# RFID_reader_v2.net
KiCad netlist of a schematic drawn in EAGLE
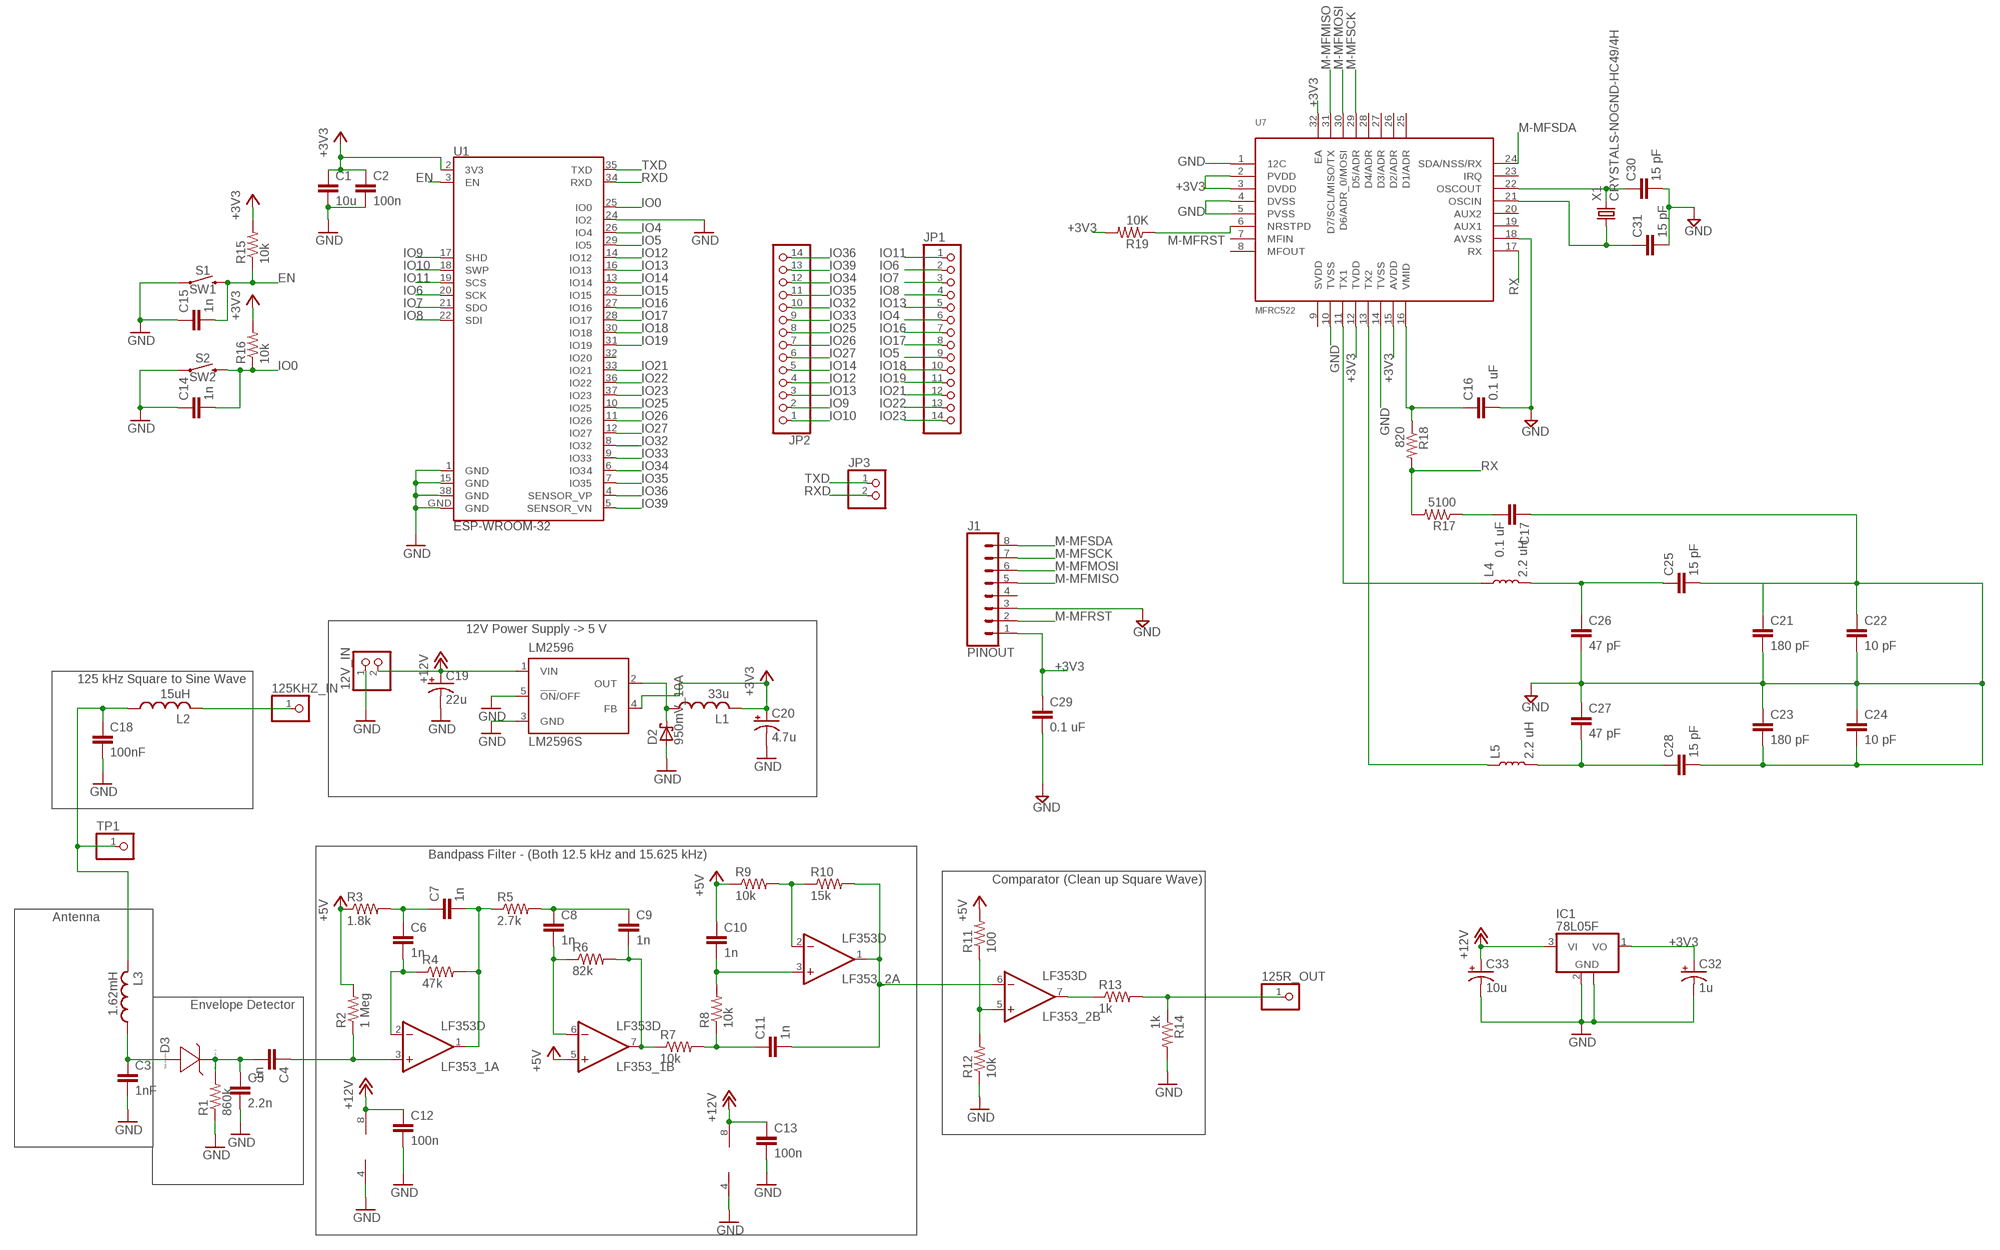
[diagram p0: schematic, sheet 1]

(export (version "E")
  (design (tool "Eeschema 10.0.6"))
  (components
    (comp (ref "12V_IN")
      (value "PINHD-1X2")
      (footprint "eagle-import:1X02")
      (libsource (lib "eagle-import") (part "PINHD-1X2"))
    )
    (comp (ref "125KHZ_IN")
      (value "PINHD-1X1")
      (footprint "eagle-import:1X01")
      (libsource (lib "eagle-import") (part "PINHD-1X1"))
    )
    (comp (ref "125R_OUT")
      (value "PINHD-1X1")
      (footprint "eagle-import:1X01")
      (libsource (lib "eagle-import") (part "PINHD-1X1"))
    )
    (comp (ref "C1")
      (value "10u")
      (footprint "eagle-import:C0805")
      (libsource (lib "eagle-import") (part "C-EUC0805"))
    )
    (comp (ref "C2")
      (value "100n")
      (footprint "eagle-import:C0805")
      (libsource (lib "eagle-import") (part "C-EUC0805"))
    )
    (comp (ref "C3")
      (value "1nF")
      (footprint "eagle-import:C0805")
      (libsource (lib "eagle-import") (part "C-EUC0805"))
    )
    (comp (ref "C4")
      (value "1n")
      (footprint "eagle-import:C0805")
      (libsource (lib "eagle-import") (part "C-EUC0805"))
    )
    (comp (ref "C5")
      (value "2.2n")
      (footprint "eagle-import:C0805")
      (libsource (lib "eagle-import") (part "C-EUC0805"))
    )
    (comp (ref "C6")
      (value "1n")
      (footprint "eagle-import:C0805")
      (libsource (lib "eagle-import") (part "C-EUC0805"))
    )
    (comp (ref "C7")
      (value "1n")
      (footprint "eagle-import:C0805")
      (libsource (lib "eagle-import") (part "C-EUC0805"))
    )
    (comp (ref "C8")
      (value "1n")
      (footprint "eagle-import:C0805")
      (libsource (lib "eagle-import") (part "C-EUC0805"))
    )
    (comp (ref "C9")
      (value "1n")
      (footprint "eagle-import:C0805")
      (libsource (lib "eagle-import") (part "C-EUC0805"))
    )
    (comp (ref "C10")
      (value "1n")
      (footprint "eagle-import:C0805")
      (libsource (lib "eagle-import") (part "C-EUC0805"))
    )
    (comp (ref "C11")
      (value "1n")
      (footprint "eagle-import:C0805")
      (libsource (lib "eagle-import") (part "C-EUC0805"))
    )
    (comp (ref "C12")
      (value "100n")
      (footprint "eagle-import:C0805")
      (libsource (lib "eagle-import") (part "C-EUC0805"))
    )
    (comp (ref "C13")
      (value "100n")
      (footprint "eagle-import:C0805")
      (libsource (lib "eagle-import") (part "C-EUC0805"))
    )
    (comp (ref "C14")
      (value "1n")
      (footprint "eagle-import:C0805")
      (libsource (lib "eagle-import") (part "C-EUC0805"))
    )
    (comp (ref "C15")
      (value "1n")
      (footprint "eagle-import:C0805")
      (libsource (lib "eagle-import") (part "C-EUC0805"))
    )
    (comp (ref "C16")
      (value "0.1 uF")
      (footprint "eagle-import:C0603")
      (libsource (lib "eagle-import") (part "C-EUC0603"))
    )
    (comp (ref "C17")
      (value "0.1 uF")
      (footprint "eagle-import:C0603")
      (libsource (lib "eagle-import") (part "C-EUC0603"))
    )
    (comp (ref "C18")
      (value "100nF")
      (footprint "eagle-import:C0805")
      (libsource (lib "eagle-import") (part "C-EUC0805"))
    )
    (comp (ref "C19")
      (value "22u")
      (footprint "eagle-import:SANYO-OSCON_SMD_B6")
      (libsource (lib "eagle-import") (part "CPOL-USSANYO_SMD_B6"))
    )
    (comp (ref "C20")
      (value "4.7u")
      (footprint "eagle-import:SMC_C")
      (libsource (lib "eagle-import") (part "CPOL-USSMCC"))
    )
    (comp (ref "C21")
      (value "180 pF")
      (footprint "eagle-import:C0603")
      (libsource (lib "eagle-import") (part "C-EUC0603"))
    )
    (comp (ref "C22")
      (value "10 pF")
      (footprint "eagle-import:C0603")
      (libsource (lib "eagle-import") (part "C-EUC0603"))
    )
    (comp (ref "C23")
      (value "180 pF")
      (footprint "eagle-import:C0603")
      (libsource (lib "eagle-import") (part "C-EUC0603"))
    )
    (comp (ref "C24")
      (value "10 pF")
      (footprint "eagle-import:C0603")
      (libsource (lib "eagle-import") (part "C-EUC0603"))
    )
    (comp (ref "C25")
      (value "15 pF")
      (footprint "eagle-import:C0603")
      (libsource (lib "eagle-import") (part "C-EUC0603"))
    )
    (comp (ref "C26")
      (value "47 pF")
      (footprint "eagle-import:C0603")
      (libsource (lib "eagle-import") (part "C-EUC0603"))
    )
    (comp (ref "C27")
      (value "47 pF")
      (footprint "eagle-import:C0603")
      (libsource (lib "eagle-import") (part "C-EUC0603"))
    )
    (comp (ref "C28")
      (value "15 pF")
      (footprint "eagle-import:C0603")
      (libsource (lib "eagle-import") (part "C-EUC0603"))
    )
    (comp (ref "C29")
      (value "0.1 uF")
      (footprint "eagle-import:C0603")
      (libsource (lib "eagle-import") (part "C-EUC0603"))
    )
    (comp (ref "C30")
      (value "15 pF")
      (footprint "eagle-import:C0603")
      (libsource (lib "eagle-import") (part "C-EUC0603"))
    )
    (comp (ref "C31")
      (value "15 pF")
      (footprint "eagle-import:C0603")
      (libsource (lib "eagle-import") (part "C-EUC0603"))
    )
    (comp (ref "C32")
      (value "1u")
      (footprint "eagle-import:SMC_A")
      (libsource (lib "eagle-import") (part "CPOL-USSMCA"))
    )
    (comp (ref "C33")
      (value "10u")
      (footprint "eagle-import:SMC_C")
      (libsource (lib "eagle-import") (part "CPOL-USSMCC"))
    )
    (comp (ref "D2")
      (value "950mV_10A")
      (footprint "eagle-import:SMC")
      (libsource (lib "eagle-import") (part "SCHOTTKY-DIODESMC"))
    )
    (comp (ref "D3")
      (value "ZENER")
      (footprint "eagle-import:SOD123")
      (libsource (lib "eagle-import") (part "ZENER"))
    )
    (comp (ref "IC1")
      (value "78L05F")
      (footprint "eagle-import:SOT89")
      (libsource (lib "eagle-import") (part "78LF05"))
    )
    (comp (ref "J1")
      (value "PINOUT")
      (footprint "eagle-import:1X08_NO_SILK")
      (libsource (lib "eagle-import") (part "CONN_08NO_SILK_FEMALE_PTH"))
    )
    (comp (ref "JP1")
      (value "PINHD-1X14")
      (footprint "eagle-import:1X14")
      (libsource (lib "eagle-import") (part "PINHD-1X14"))
    )
    (comp (ref "JP2")
      (value "PINHD-1X14")
      (footprint "eagle-import:1X14")
      (libsource (lib "eagle-import") (part "PINHD-1X14"))
    )
    (comp (ref "JP3")
      (value "PINHD-1X2")
      (footprint "eagle-import:1X02")
      (libsource (lib "eagle-import") (part "PINHD-1X2"))
    )
    (comp (ref "L1")
      (value "33u")
      (footprint "eagle-import:0207_10")
      (libsource (lib "eagle-import") (part "L-US0207/10"))
    )
    (comp (ref "L2")
      (value "15uH")
      (footprint "eagle-import:L2012C")
      (libsource (lib "eagle-import") (part "L-USL2012C"))
    )
    (comp (ref "L3")
      (value "1.62mH")
      (footprint "eagle-import:0207_10")
      (libsource (lib "eagle-import") (part "L-US0207/10"))
    )
    (comp (ref "L4")
      (value "2.2 uH")
      (footprint "eagle-import:0603")
      (libsource (lib "eagle-import") (part "INDUCTOR-0603-33NH"))
    )
    (comp (ref "L5")
      (value "2.2 uH")
      (footprint "eagle-import:0603")
      (libsource (lib "eagle-import") (part "INDUCTOR-0603-33NH"))
    )
    (comp (ref "LF353_1")
      (value "LF353D")
      (footprint "eagle-import:SO08")
      (fields (field (name "SPICEPREFIX") "J"))
      (libsource (lib "eagle-import") (part "LF353D"))
    )
    (comp (ref "LF353_2")
      (value "LF353D")
      (footprint "eagle-import:SO08")
      (libsource (lib "eagle-import") (part "LF353D"))
    )
    (comp (ref "LM2596")
      (value "LM2596S")
      (footprint "eagle-import:TO263-5")
      (fields (field (name "MF") "NATIONAL SEMICONDUCTOR") (field (name "MPN") "LM2596S-ADJ/NOPB"))
      (libsource (lib "eagle-import") (part "LM2596S"))
    )
    (comp (ref "R1")
      (value "860k")
      (footprint "eagle-import:R0805")
      (libsource (lib "eagle-import") (part "R-US_R0805"))
    )
    (comp (ref "R2")
      (value "1 Meg")
      (footprint "eagle-import:R0805")
      (libsource (lib "eagle-import") (part "R-US_R0805"))
    )
    (comp (ref "R3")
      (value "1.8k")
      (footprint "eagle-import:R0805")
      (libsource (lib "eagle-import") (part "R-US_R0805"))
    )
    (comp (ref "R4")
      (value "47k")
      (footprint "eagle-import:R0805")
      (libsource (lib "eagle-import") (part "R-US_R0805"))
    )
    (comp (ref "R5")
      (value "2.7k")
      (footprint "eagle-import:R0805")
      (libsource (lib "eagle-import") (part "R-US_R0805"))
    )
    (comp (ref "R6")
      (value "82k")
      (footprint "eagle-import:R0805")
      (libsource (lib "eagle-import") (part "R-US_R0805"))
    )
    (comp (ref "R7")
      (value "10k")
      (footprint "eagle-import:R0805")
      (libsource (lib "eagle-import") (part "R-US_R0805"))
    )
    (comp (ref "R8")
      (value "10k")
      (footprint "eagle-import:R0805")
      (libsource (lib "eagle-import") (part "R-US_R0805"))
    )
    (comp (ref "R9")
      (value "10k")
      (footprint "eagle-import:R0805")
      (libsource (lib "eagle-import") (part "R-US_R0805"))
    )
    (comp (ref "R10")
      (value "15k")
      (footprint "eagle-import:R0805")
      (libsource (lib "eagle-import") (part "R-US_R0805"))
    )
    (comp (ref "R11")
      (value "100")
      (footprint "eagle-import:R0805")
      (libsource (lib "eagle-import") (part "R-US_R0805"))
    )
    (comp (ref "R12")
      (value "10k")
      (footprint "eagle-import:R0805")
      (libsource (lib "eagle-import") (part "R-US_R0805"))
    )
    (comp (ref "R13")
      (value "1k")
      (footprint "eagle-import:R0805")
      (libsource (lib "eagle-import") (part "R-US_R0805"))
    )
    (comp (ref "R14")
      (value "1k")
      (footprint "eagle-import:R0805")
      (libsource (lib "eagle-import") (part "R-US_R0805"))
    )
    (comp (ref "R15")
      (value "10k")
      (footprint "eagle-import:R0805")
      (libsource (lib "eagle-import") (part "R-US_R0805"))
    )
    (comp (ref "R16")
      (value "10k")
      (footprint "eagle-import:R0805")
      (libsource (lib "eagle-import") (part "R-US_R0805"))
    )
    (comp (ref "R17")
      (value "5100")
      (footprint "eagle-import:R0603")
      (libsource (lib "eagle-import") (part "R-US_R0603"))
    )
    (comp (ref "R18")
      (value "820")
      (footprint "eagle-import:R0603")
      (libsource (lib "eagle-import") (part "R-US_R0603"))
    )
    (comp (ref "R19")
      (value "10K")
      (footprint "eagle-import:R0603")
      (libsource (lib "eagle-import") (part "R-US_R0603"))
    )
    (comp (ref "S1")
      (value "SW1")
      (footprint "eagle-import:TACTILE_SWITCH_SMD_6.0X3.5MM")
      (libsource (lib "eagle-import") (part "MOMENTARY-SWITCH-SPST-SMD-6.0X3.5MM"))
    )
    (comp (ref "S2")
      (value "SW2")
      (footprint "eagle-import:TACTILE_SWITCH_SMD_6.0X3.5MM")
      (libsource (lib "eagle-import") (part "MOMENTARY-SWITCH-SPST-SMD-6.0X3.5MM"))
    )
    (comp (ref "TP1")
      (value "PINHD-1X1")
      (footprint "eagle-import:1X01")
      (libsource (lib "eagle-import") (part "PINHD-1X1"))
    )
    (comp (ref "U1")
      (value "ESP-WROOM-32")
      (footprint "eagle-import:ESP-WROOM-32")
      (libsource (lib "eagle-import") (part "ESP-WROOM-32"))
    )
    (comp (ref "U7")
      (value "MFRC522")
      (footprint "eagle-import:MFR522")
      (libsource (lib "eagle-import") (part "MFRC522"))
    )
    (comp (ref "X1")
      (value "CRYSTALS-NOGND-HC49/4H")
      (footprint "eagle-import:HC49")
      (libsource (lib "eagle-import") (part "CRYSTALS-NOGND-HC49/4H"))
    )
  )
  (nets
    (net (code "1") (name "+3V3") (class "Default")
      (node (ref "C1") (pin "1") (pinfunction "1_1") (pintype "passive"))
      (node (ref "C2") (pin "1") (pinfunction "1_1") (pintype "passive"))
      (node (ref "C20") (pin "+") (pinfunction "+_+") (pintype "passive"))
      (node (ref "C29") (pin "1") (pinfunction "1_1") (pintype "passive"))
      (node (ref "C32") (pin "+") (pinfunction "+_+") (pintype "passive"))
      (node (ref "IC1") (pin "1") (pinfunction "VO_1") (pintype "passive"))
      (node (ref "J1") (pin "1") (pinfunction "1_1") (pintype "passive"))
      (node (ref "L1") (pin "2") (pinfunction "2_2") (pintype "passive"))
      (node (ref "LM2596") (pin "4") (pinfunction "FB_4") (pintype "input"))
      (node (ref "R15") (pin "2") (pinfunction "2_2") (pintype "passive"))
      (node (ref "R16") (pin "2") (pinfunction "2_2") (pintype "passive"))
      (node (ref "R19") (pin "2") (pinfunction "2_2") (pintype "passive"))
      (node (ref "U1") (pin "2") (pinfunction "3V3_2") (pintype "bidirectional"))
      (node (ref "U7") (pin "12") (pinfunction "TVDD_12") (pintype "bidirectional"))
      (node (ref "U7") (pin "15") (pinfunction "AVDD_15") (pintype "bidirectional"))
      (node (ref "U7") (pin "2") (pinfunction "PVDD_2") (pintype "bidirectional"))
      (node (ref "U7") (pin "3") (pinfunction "DVDD_3") (pintype "bidirectional"))
      (node (ref "U7") (pin "32") (pinfunction "EA_32") (pintype "bidirectional"))
    )
    (net (code "2") (name "+5V") (class "Default")
      (node (ref "C10") (pin "1") (pinfunction "1_1") (pintype "passive"))
      (node (ref "LF353_1") (pin "5") (pinfunction "+IN_5") (pintype "input"))
      (node (ref "R11") (pin "2") (pinfunction "2_2") (pintype "passive"))
      (node (ref "R2") (pin "2") (pinfunction "2_2") (pintype "passive"))
      (node (ref "R3") (pin "1") (pinfunction "1_1") (pintype "passive"))
      (node (ref "R9") (pin "1") (pinfunction "1_1") (pintype "passive"))
    )
    (net (code "3") (name "+12V") (class "Default")
      (node (ref "12V_IN") (pin "2") (pinfunction "2_2") (pintype "passive"))
      (node (ref "C12") (pin "1") (pinfunction "1_1") (pintype "passive"))
      (node (ref "C13") (pin "1") (pinfunction "1_1") (pintype "passive"))
      (node (ref "C19") (pin "+") (pinfunction "+_+") (pintype "passive"))
      (node (ref "C33") (pin "+") (pinfunction "+_+") (pintype "passive"))
      (node (ref "IC1") (pin "3") (pinfunction "VI_3") (pintype "input"))
      (node (ref "LF353_1") (pin "8") (pinfunction "V+_8") (pintype "power_in"))
      (node (ref "LF353_2") (pin "8") (pinfunction "V+_8") (pintype "power_in"))
      (node (ref "LM2596") (pin "1") (pinfunction "VIN_1") (pintype "input"))
    )
    (net (code "4") (name "/EN") (class "Default")
      (node (ref "C15") (pin "2") (pinfunction "2_2") (pintype "passive"))
      (node (ref "R15") (pin "1") (pinfunction "1_1") (pintype "passive"))
      (node (ref "S1") (pin "2") (pinfunction "2_2") (pintype "passive"))
      (node (ref "U1") (pin "3") (pinfunction "EN_3") (pintype "bidirectional"))
    )
    (net (code "5") (name "/IO0") (class "Default")
      (node (ref "C14") (pin "2") (pinfunction "2_2") (pintype "passive"))
      (node (ref "R16") (pin "1") (pinfunction "1_1") (pintype "passive"))
      (node (ref "S2") (pin "2") (pinfunction "2_2") (pintype "passive"))
      (node (ref "U1") (pin "25") (pinfunction "IO0_25") (pintype "bidirectional"))
    )
    (net (code "6") (name "/IO4") (class "Default")
      (node (ref "JP1") (pin "6") (pinfunction "6_6") (pintype "passive"))
      (node (ref "U1") (pin "26") (pinfunction "IO4_26") (pintype "bidirectional"))
    )
    (net (code "7") (name "/IO5") (class "Default")
      (node (ref "JP1") (pin "9") (pinfunction "9_9") (pintype "passive"))
      (node (ref "U1") (pin "29") (pinfunction "IO5_29") (pintype "bidirectional"))
    )
    (net (code "8") (name "/IO6") (class "Default")
      (node (ref "JP1") (pin "2") (pinfunction "2_2") (pintype "passive"))
      (node (ref "U1") (pin "20") (pinfunction "SCK_20") (pintype "bidirectional"))
    )
    (net (code "9") (name "/IO7") (class "Default")
      (node (ref "JP1") (pin "3") (pinfunction "3_3") (pintype "passive"))
      (node (ref "U1") (pin "21") (pinfunction "SDO_21") (pintype "bidirectional"))
    )
    (net (code "10") (name "/IO8") (class "Default")
      (node (ref "JP1") (pin "4") (pinfunction "4_4") (pintype "passive"))
      (node (ref "U1") (pin "22") (pinfunction "SDI_22") (pintype "bidirectional"))
    )
    (net (code "11") (name "/IO9") (class "Default")
      (node (ref "JP2") (pin "2") (pinfunction "2_2") (pintype "passive"))
      (node (ref "U1") (pin "17") (pinfunction "SHD_17") (pintype "bidirectional"))
    )
    (net (code "12") (name "/IO10") (class "Default")
      (node (ref "JP2") (pin "1") (pinfunction "1_1") (pintype "passive"))
      (node (ref "U1") (pin "18") (pinfunction "SWP_18") (pintype "bidirectional"))
    )
    (net (code "13") (name "/IO11") (class "Default")
      (node (ref "JP1") (pin "1") (pinfunction "1_1") (pintype "passive"))
      (node (ref "U1") (pin "19") (pinfunction "SCS_19") (pintype "bidirectional"))
    )
    (net (code "14") (name "/IO12") (class "Default")
      (node (ref "JP2") (pin "4") (pinfunction "4_4") (pintype "passive"))
      (node (ref "U1") (pin "14") (pinfunction "IO12_14") (pintype "bidirectional"))
    )
    (net (code "15") (name "/IO13") (class "Default")
      (node (ref "JP1") (pin "5") (pinfunction "5_5") (pintype "passive"))
      (node (ref "JP2") (pin "3") (pinfunction "3_3") (pintype "passive"))
      (node (ref "U1") (pin "16") (pinfunction "IO13_16") (pintype "bidirectional"))
    )
    (net (code "16") (name "/IO14") (class "Default")
      (node (ref "JP2") (pin "5") (pinfunction "5_5") (pintype "passive"))
      (node (ref "U1") (pin "13") (pinfunction "IO14_13") (pintype "bidirectional"))
    )
    (net (code "17") (name "/IO15") (class "Default")
      (node (ref "U1") (pin "23") (pinfunction "IO15_23") (pintype "bidirectional"))
    )
    (net (code "18") (name "/IO16") (class "Default")
      (node (ref "JP1") (pin "7") (pinfunction "7_7") (pintype "passive"))
      (node (ref "U1") (pin "27") (pinfunction "IO16_27") (pintype "bidirectional"))
    )
    (net (code "19") (name "/IO17") (class "Default")
      (node (ref "JP1") (pin "8") (pinfunction "8_8") (pintype "passive"))
      (node (ref "U1") (pin "28") (pinfunction "IO17_28") (pintype "bidirectional"))
    )
    (net (code "20") (name "/IO18") (class "Default")
      (node (ref "JP1") (pin "10") (pinfunction "10_10") (pintype "passive"))
      (node (ref "U1") (pin "30") (pinfunction "IO18_30") (pintype "bidirectional"))
    )
    (net (code "21") (name "/IO19") (class "Default")
      (node (ref "JP1") (pin "11") (pinfunction "11_11") (pintype "passive"))
      (node (ref "U1") (pin "31") (pinfunction "IO19_31") (pintype "bidirectional"))
    )
    (net (code "22") (name "/IO21") (class "Default")
      (node (ref "JP1") (pin "12") (pinfunction "12_12") (pintype "passive"))
      (node (ref "U1") (pin "33") (pinfunction "IO21_33") (pintype "bidirectional"))
    )
    (net (code "23") (name "/IO22") (class "Default")
      (node (ref "JP1") (pin "13") (pinfunction "13_13") (pintype "passive"))
      (node (ref "U1") (pin "36") (pinfunction "IO22_36") (pintype "bidirectional"))
    )
    (net (code "24") (name "/IO23") (class "Default")
      (node (ref "JP1") (pin "14") (pinfunction "14_14") (pintype "passive"))
      (node (ref "U1") (pin "37") (pinfunction "IO23_37") (pintype "bidirectional"))
    )
    (net (code "25") (name "/IO25") (class "Default")
      (node (ref "JP2") (pin "8") (pinfunction "8_8") (pintype "passive"))
      (node (ref "U1") (pin "10") (pinfunction "IO25_10") (pintype "bidirectional"))
    )
    (net (code "26") (name "/IO26") (class "Default")
      (node (ref "JP2") (pin "7") (pinfunction "7_7") (pintype "passive"))
      (node (ref "U1") (pin "11") (pinfunction "IO26_11") (pintype "bidirectional"))
    )
    (net (code "27") (name "/IO27") (class "Default")
      (node (ref "JP2") (pin "6") (pinfunction "6_6") (pintype "passive"))
      (node (ref "U1") (pin "12") (pinfunction "IO27_12") (pintype "bidirectional"))
    )
    (net (code "28") (name "/IO32") (class "Default")
      (node (ref "JP2") (pin "10") (pinfunction "10_10") (pintype "passive"))
      (node (ref "U1") (pin "8") (pinfunction "IO32_8") (pintype "bidirectional"))
    )
    (net (code "29") (name "/IO33") (class "Default")
      (node (ref "JP2") (pin "9") (pinfunction "9_9") (pintype "passive"))
      (node (ref "U1") (pin "9") (pinfunction "IO33_9") (pintype "bidirectional"))
    )
    (net (code "30") (name "/IO34") (class "Default")
      (node (ref "JP2") (pin "12") (pinfunction "12_12") (pintype "passive"))
      (node (ref "U1") (pin "6") (pinfunction "IO34_6") (pintype "bidirectional"))
    )
    (net (code "31") (name "/IO35") (class "Default")
      (node (ref "JP2") (pin "11") (pinfunction "11_11") (pintype "passive"))
      (node (ref "U1") (pin "7") (pinfunction "IO35_7") (pintype "bidirectional"))
    )
    (net (code "32") (name "/IO36") (class "Default")
      (node (ref "JP2") (pin "14") (pinfunction "14_14") (pintype "passive"))
      (node (ref "U1") (pin "4") (pinfunction "SENSOR_VP_4") (pintype "bidirectional"))
    )
    (net (code "33") (name "/IO39") (class "Default")
      (node (ref "JP2") (pin "13") (pinfunction "13_13") (pintype "passive"))
      (node (ref "U1") (pin "5") (pinfunction "SENSOR_VN_5") (pintype "bidirectional"))
    )
    (net (code "34") (name "/M-MFMISO") (class "Default")
      (node (ref "J1") (pin "5") (pinfunction "5_5") (pintype "passive"))
      (node (ref "U7") (pin "31") (pinfunction "D7/SCL/MISO/TX_31") (pintype "bidirectional"))
    )
    (net (code "35") (name "/M-MFMOSI") (class "Default")
      (node (ref "J1") (pin "6") (pinfunction "6_6") (pintype "passive"))
      (node (ref "U7") (pin "30") (pinfunction "D6/ADR_0/MOSI_30") (pintype "bidirectional"))
    )
    (net (code "36") (name "/M-MFRST") (class "Default")
      (node (ref "J1") (pin "2") (pinfunction "2_2") (pintype "passive"))
      (node (ref "R19") (pin "1") (pinfunction "1_1") (pintype "passive"))
      (node (ref "U7") (pin "6") (pinfunction "NRSTPD_6") (pintype "bidirectional"))
    )
    (net (code "37") (name "/M-MFSCK") (class "Default")
      (node (ref "J1") (pin "7") (pinfunction "7_7") (pintype "passive"))
      (node (ref "U7") (pin "29") (pinfunction "D5/ADR_29") (pintype "bidirectional"))
    )
    (net (code "38") (name "/M-MFSDA") (class "Default")
      (node (ref "J1") (pin "8") (pinfunction "8_8") (pintype "passive"))
      (node (ref "U7") (pin "24") (pinfunction "SDA/NSS/RX_24") (pintype "bidirectional"))
    )
    (net (code "39") (name "/RX") (class "Default")
      (node (ref "R17") (pin "2") (pinfunction "2_2") (pintype "passive"))
      (node (ref "R18") (pin "2") (pinfunction "2_2") (pintype "passive"))
      (node (ref "U7") (pin "17") (pinfunction "RX_17") (pintype "bidirectional"))
    )
    (net (code "40") (name "/RXD") (class "Default")
      (node (ref "JP3") (pin "2") (pinfunction "2_2") (pintype "passive"))
      (node (ref "U1") (pin "34") (pinfunction "RXD_34") (pintype "bidirectional"))
    )
    (net (code "41") (name "/TXD") (class "Default")
      (node (ref "JP3") (pin "1") (pinfunction "1_1") (pintype "passive"))
      (node (ref "U1") (pin "35") (pinfunction "TXD_35") (pintype "bidirectional"))
    )
    (net (code "42") (name "GND") (class "Default")
      (node (ref "12V_IN") (pin "1") (pinfunction "1_1") (pintype "passive"))
      (node (ref "C1") (pin "2") (pinfunction "2_2") (pintype "passive"))
      (node (ref "C12") (pin "2") (pinfunction "2_2") (pintype "passive"))
      (node (ref "C13") (pin "2") (pinfunction "2_2") (pintype "passive"))
      (node (ref "C14") (pin "1") (pinfunction "1_1") (pintype "passive"))
      (node (ref "C15") (pin "1") (pinfunction "1_1") (pintype "passive"))
      (node (ref "C16") (pin "2") (pinfunction "2_2") (pintype "passive"))
      (node (ref "C17") (pin "1") (pinfunction "1_1") (pintype "passive"))
      (node (ref "C18") (pin "2") (pinfunction "2_2") (pintype "passive"))
      (node (ref "C19") (pin "-") (pinfunction "-_-") (pintype "passive"))
      (node (ref "C2") (pin "2") (pinfunction "2_2") (pintype "passive"))
      (node (ref "C20") (pin "-") (pinfunction "-_-") (pintype "passive"))
      (node (ref "C21") (pin "1") (pinfunction "1_1") (pintype "passive"))
      (node (ref "C21") (pin "2") (pinfunction "2_2") (pintype "passive"))
      (node (ref "C22") (pin "1") (pinfunction "1_1") (pintype "passive"))
      (node (ref "C22") (pin "2") (pinfunction "2_2") (pintype "passive"))
      (node (ref "C23") (pin "1") (pinfunction "1_1") (pintype "passive"))
      (node (ref "C23") (pin "2") (pinfunction "2_2") (pintype "passive"))
      (node (ref "C24") (pin "1") (pinfunction "1_1") (pintype "passive"))
      (node (ref "C24") (pin "2") (pinfunction "2_2") (pintype "passive"))
      (node (ref "C25") (pin "2") (pinfunction "2_2") (pintype "passive"))
      (node (ref "C26") (pin "2") (pinfunction "2_2") (pintype "passive"))
      (node (ref "C27") (pin "1") (pinfunction "1_1") (pintype "passive"))
      (node (ref "C28") (pin "2") (pinfunction "2_2") (pintype "passive"))
      (node (ref "C29") (pin "2") (pinfunction "2_2") (pintype "passive"))
      (node (ref "C3") (pin "2") (pinfunction "2_2") (pintype "passive"))
      (node (ref "C30") (pin "2") (pinfunction "2_2") (pintype "passive"))
      (node (ref "C31") (pin "2") (pinfunction "2_2") (pintype "passive"))
      (node (ref "C32") (pin "-") (pinfunction "-_-") (pintype "passive"))
      (node (ref "C33") (pin "-") (pinfunction "-_-") (pintype "passive"))
      (node (ref "C5") (pin "2") (pinfunction "2_2") (pintype "passive"))
      (node (ref "D2") (pin "A") (pinfunction "A_A") (pintype "passive"))
      (node (ref "IC1") (pin "2") (pinfunction "GND_2") (pintype "passive"))
      (node (ref "IC1") (pin "2@1") (pinfunction "GND_2@1") (pintype "passive"))
      (node (ref "J1") (pin "3") (pinfunction "3_3") (pintype "passive"))
      (node (ref "LF353_1") (pin "4") (pinfunction "V-_4") (pintype "power_in"))
      (node (ref "LF353_2") (pin "4") (pinfunction "V-_4") (pintype "power_in"))
      (node (ref "LM2596") (pin "3") (pinfunction "GND_3") (pintype "power_in"))
      (node (ref "LM2596") (pin "5") (pinfunction "~{ON}/OFF_5") (pintype "input"))
      (node (ref "R1") (pin "1") (pinfunction "1_1") (pintype "passive"))
      (node (ref "R12") (pin "1") (pinfunction "1_1") (pintype "passive"))
      (node (ref "R14") (pin "2") (pinfunction "2_2") (pintype "passive"))
      (node (ref "S1") (pin "1") (pinfunction "1_1") (pintype "passive"))
      (node (ref "S2") (pin "1") (pinfunction "1_1") (pintype "passive"))
      (node (ref "U1") (pin "1") (pinfunction "GND_1") (pintype "bidirectional"))
      (node (ref "U1") (pin "15") (pinfunction "GND_15") (pintype "bidirectional"))
      (node (ref "U1") (pin "24") (pinfunction "IO2_24") (pintype "bidirectional"))
      (node (ref "U1") (pin "38") (pinfunction "GND_38") (pintype "bidirectional"))
      (node (ref "U1") (pin "GND") (pinfunction "GND_GND") (pintype "bidirectional"))
      (node (ref "U7") (pin "1") (pinfunction "12C_1") (pintype "bidirectional"))
      (node (ref "U7") (pin "10") (pinfunction "TVSS_10") (pintype "bidirectional"))
      (node (ref "U7") (pin "14") (pinfunction "TVSS_14") (pintype "bidirectional"))
      (node (ref "U7") (pin "18") (pinfunction "AVSS_18") (pintype "bidirectional"))
      (node (ref "U7") (pin "4") (pinfunction "DVSS_4") (pintype "bidirectional"))
      (node (ref "U7") (pin "5") (pinfunction "PVSS_5") (pintype "bidirectional"))
    )
    (net (code "43") (name "Net-(125KHZ_IN-Pad1)") (class "Default")
      (node (ref "125KHZ_IN") (pin "1") (pinfunction "1_1") (pintype "passive"))
      (node (ref "L2") (pin "2") (pinfunction "2_2") (pintype "passive"))
    )
    (net (code "44") (name "Net-(125R_OUT-Pad1)") (class "Default")
      (node (ref "125R_OUT") (pin "1") (pinfunction "1_1") (pintype "passive"))
      (node (ref "R13") (pin "2") (pinfunction "2_2") (pintype "passive"))
      (node (ref "R14") (pin "1") (pinfunction "1_1") (pintype "passive"))
    )
    (net (code "45") (name "Net-(C6-Pad1)") (class "Default")
      (node (ref "C6") (pin "1") (pinfunction "1_1") (pintype "passive"))
      (node (ref "C7") (pin "1") (pinfunction "1_1") (pintype "passive"))
      (node (ref "R3") (pin "2") (pinfunction "2_2") (pintype "passive"))
    )
    (net (code "46") (name "Net-(C8-Pad1)") (class "Default")
      (node (ref "C8") (pin "1") (pinfunction "1_1") (pintype "passive"))
      (node (ref "C9") (pin "1") (pinfunction "1_1") (pintype "passive"))
      (node (ref "R5") (pin "2") (pinfunction "2_2") (pintype "passive"))
    )
    (net (code "47") (name "Net-(C11-Pad1)") (class "Default")
      (node (ref "C11") (pin "1") (pinfunction "1_1") (pintype "passive"))
      (node (ref "R7") (pin "2") (pinfunction "2_2") (pintype "passive"))
      (node (ref "R8") (pin "1") (pinfunction "1_1") (pintype "passive"))
    )
    (net (code "48") (name "Net-(C17-Pad2)") (class "Default")
      (node (ref "C17") (pin "2") (pinfunction "2_2") (pintype "passive"))
      (node (ref "R17") (pin "1") (pinfunction "1_1") (pintype "passive"))
    )
    (net (code "49") (name "Net-(C18-Pad1)") (class "Default")
      (node (ref "C18") (pin "1") (pinfunction "1_1") (pintype "passive"))
      (node (ref "L2") (pin "1") (pinfunction "1_1") (pintype "passive"))
      (node (ref "L3") (pin "2") (pinfunction "2_2") (pintype "passive"))
      (node (ref "TP1") (pin "1") (pinfunction "1_1") (pintype "passive"))
    )
    (net (code "50") (name "Net-(C25-Pad1)") (class "Default")
      (node (ref "C25") (pin "1") (pinfunction "1_1") (pintype "passive"))
      (node (ref "C26") (pin "1") (pinfunction "1_1") (pintype "passive"))
      (node (ref "L4") (pin "2") (pinfunction "2_2") (pintype "passive"))
    )
    (net (code "51") (name "Net-(C27-Pad2)") (class "Default")
      (node (ref "C27") (pin "2") (pinfunction "2_2") (pintype "passive"))
      (node (ref "C28") (pin "1") (pinfunction "1_1") (pintype "passive"))
      (node (ref "L5") (pin "2") (pinfunction "2_2") (pintype "passive"))
    )
    (net (code "52") (name "Net-(D3-+)") (class "Default")
      (node (ref "C3") (pin "1") (pinfunction "1_1") (pintype "passive"))
      (node (ref "D3") (pin "A") (pinfunction "+_A") (pintype "passive"))
      (node (ref "L3") (pin "1") (pinfunction "1_1") (pintype "passive"))
    )
    (net (code "53") (name "Net-(D3--)") (class "Default")
      (node (ref "C4") (pin "2") (pinfunction "2_2") (pintype "passive"))
      (node (ref "C5") (pin "1") (pinfunction "1_1") (pintype "passive"))
      (node (ref "D3") (pin "C") (pinfunction "-_C") (pintype "passive"))
      (node (ref "R1") (pin "2") (pinfunction "2_2") (pintype "passive"))
    )
    (net (code "54") (name "Net-(LF353_1A-+IN)") (class "Default")
      (node (ref "C4") (pin "1") (pinfunction "1_1") (pintype "passive"))
      (node (ref "LF353_1") (pin "3") (pinfunction "+IN_3") (pintype "input"))
      (node (ref "R2") (pin "1") (pinfunction "1_1") (pintype "passive"))
    )
    (net (code "55") (name "Net-(LF353_1A--IN)") (class "Default")
      (node (ref "C6") (pin "2") (pinfunction "2_2") (pintype "passive"))
      (node (ref "LF353_1") (pin "2") (pinfunction "-IN_2") (pintype "input"))
      (node (ref "R4") (pin "1") (pinfunction "1_1") (pintype "passive"))
    )
    (net (code "56") (name "Net-(LF353_1A-OUT)") (class "Default")
      (node (ref "C7") (pin "2") (pinfunction "2_2") (pintype "passive"))
      (node (ref "LF353_1") (pin "1") (pinfunction "OUT_1") (pintype "output"))
      (node (ref "R4") (pin "2") (pinfunction "2_2") (pintype "passive"))
      (node (ref "R5") (pin "1") (pinfunction "1_1") (pintype "passive"))
    )
    (net (code "57") (name "Net-(LF353_1B--IN)") (class "Default")
      (node (ref "C8") (pin "2") (pinfunction "2_2") (pintype "passive"))
      (node (ref "LF353_1") (pin "6") (pinfunction "-IN_6") (pintype "input"))
      (node (ref "R6") (pin "1") (pinfunction "1_1") (pintype "passive"))
    )
    (net (code "58") (name "Net-(LF353_1B-OUT)") (class "Default")
      (node (ref "C9") (pin "2") (pinfunction "2_2") (pintype "passive"))
      (node (ref "LF353_1") (pin "7") (pinfunction "OUT_7") (pintype "output"))
      (node (ref "R6") (pin "2") (pinfunction "2_2") (pintype "passive"))
      (node (ref "R7") (pin "1") (pinfunction "1_1") (pintype "passive"))
    )
    (net (code "59") (name "Net-(LF353_2A-+IN)") (class "Default")
      (node (ref "C10") (pin "2") (pinfunction "2_2") (pintype "passive"))
      (node (ref "LF353_2") (pin "3") (pinfunction "+IN_3") (pintype "input"))
      (node (ref "R8") (pin "2") (pinfunction "2_2") (pintype "passive"))
    )
    (net (code "60") (name "Net-(LF353_2A--IN)") (class "Default")
      (node (ref "LF353_2") (pin "2") (pinfunction "-IN_2") (pintype "input"))
      (node (ref "R10") (pin "1") (pinfunction "1_1") (pintype "passive"))
      (node (ref "R9") (pin "2") (pinfunction "2_2") (pintype "passive"))
    )
    (net (code "61") (name "Net-(LF353_2A-OUT)") (class "Default")
      (node (ref "C11") (pin "2") (pinfunction "2_2") (pintype "passive"))
      (node (ref "LF353_2") (pin "1") (pinfunction "OUT_1") (pintype "output"))
      (node (ref "LF353_2") (pin "6") (pinfunction "-IN_6") (pintype "input"))
      (node (ref "R10") (pin "2") (pinfunction "2_2") (pintype "passive"))
    )
    (net (code "62") (name "Net-(LF353_2B-+IN)") (class "Default")
      (node (ref "LF353_2") (pin "5") (pinfunction "+IN_5") (pintype "input"))
      (node (ref "R11") (pin "1") (pinfunction "1_1") (pintype "passive"))
      (node (ref "R12") (pin "2") (pinfunction "2_2") (pintype "passive"))
    )
    (net (code "63") (name "Net-(LF353_2B-OUT)") (class "Default")
      (node (ref "LF353_2") (pin "7") (pinfunction "OUT_7") (pintype "output"))
      (node (ref "R13") (pin "1") (pinfunction "1_1") (pintype "passive"))
    )
    (net (code "64") (name "Net-(LM2596-OUT)") (class "Default")
      (node (ref "D2") (pin "C") (pinfunction "C_C") (pintype "passive"))
      (node (ref "L1") (pin "1") (pinfunction "1_1") (pintype "passive"))
      (node (ref "LM2596") (pin "2") (pinfunction "OUT_2") (pintype "output"))
    )
    (net (code "65") (name "Net-(U7-OSCIN)") (class "Default")
      (node (ref "C31") (pin "1") (pinfunction "1_1") (pintype "passive"))
      (node (ref "U7") (pin "21") (pinfunction "OSCIN_21") (pintype "bidirectional"))
      (node (ref "X1") (pin "1") (pinfunction "1_1") (pintype "passive"))
    )
    (net (code "66") (name "Net-(U7-OSCOUT)") (class "Default")
      (node (ref "C30") (pin "1") (pinfunction "1_1") (pintype "passive"))
      (node (ref "U7") (pin "22") (pinfunction "OSCOUT_22") (pintype "bidirectional"))
      (node (ref "X1") (pin "2") (pinfunction "2_2") (pintype "passive"))
    )
    (net (code "67") (name "Net-(U7-TX1)") (class "Default")
      (node (ref "L4") (pin "1") (pinfunction "1_1") (pintype "passive"))
      (node (ref "U7") (pin "11") (pinfunction "TX1_11") (pintype "bidirectional"))
    )
    (net (code "68") (name "Net-(U7-TX2)") (class "Default")
      (node (ref "L5") (pin "1") (pinfunction "1_1") (pintype "passive"))
      (node (ref "U7") (pin "13") (pinfunction "TX2_13") (pintype "bidirectional"))
    )
    (net (code "69") (name "Net-(U7-VMID)") (class "Default")
      (node (ref "C16") (pin "1") (pinfunction "1_1") (pintype "passive"))
      (node (ref "R18") (pin "1") (pinfunction "1_1") (pintype "passive"))
      (node (ref "U7") (pin "16") (pinfunction "VMID_16") (pintype "bidirectional"))
    )
    (net (code "70") (name "unconnected-(J1-Pad4)") (class "Default")
      (node (ref "J1") (pin "4") (pinfunction "4_4") (pintype "passive"))
    )
    (net (code "71") (name "unconnected-(U1-IO20-Pad32)") (class "Default")
      (node (ref "U1") (pin "32") (pinfunction "IO20_32") (pintype "bidirectional"))
    )
    (net (code "72") (name "unconnected-(U7-AUX1-Pad19)") (class "Default")
      (node (ref "U7") (pin "19") (pinfunction "AUX1_19") (pintype "bidirectional"))
    )
    (net (code "73") (name "unconnected-(U7-AUX2-Pad20)") (class "Default")
      (node (ref "U7") (pin "20") (pinfunction "AUX2_20") (pintype "bidirectional"))
    )
    (net (code "74") (name "unconnected-(U7-D1{slash}ADR-Pad25)") (class "Default")
      (node (ref "U7") (pin "25") (pinfunction "D1/ADR_25") (pintype "bidirectional"))
    )
    (net (code "75") (name "unconnected-(U7-D2{slash}ADR-Pad26)") (class "Default")
      (node (ref "U7") (pin "26") (pinfunction "D2/ADR_26") (pintype "bidirectional"))
    )
    (net (code "76") (name "unconnected-(U7-D3{slash}ADR-Pad27)") (class "Default")
      (node (ref "U7") (pin "27") (pinfunction "D3/ADR_27") (pintype "bidirectional"))
    )
    (net (code "77") (name "unconnected-(U7-D4{slash}ADR-Pad28)") (class "Default")
      (node (ref "U7") (pin "28") (pinfunction "D4/ADR_28") (pintype "bidirectional"))
    )
    (net (code "78") (name "unconnected-(U7-IRQ-Pad23)") (class "Default")
      (node (ref "U7") (pin "23") (pinfunction "IRQ_23") (pintype "bidirectional"))
    )
    (net (code "79") (name "unconnected-(U7-MFIN-Pad7)") (class "Default")
      (node (ref "U7") (pin "7") (pinfunction "MFIN_7") (pintype "bidirectional"))
    )
    (net (code "80") (name "unconnected-(U7-MFOUT-Pad8)") (class "Default")
      (node (ref "U7") (pin "8") (pinfunction "MFOUT_8") (pintype "bidirectional"))
    )
    (net (code "81") (name "unconnected-(U7-SVDD-Pad9)") (class "Default")
      (node (ref "U7") (pin "9") (pinfunction "SVDD_9") (pintype "bidirectional"))
    )
  )
)
